# bluetooth.net
KiCad netlist of a schematic drawn in Altium Designer
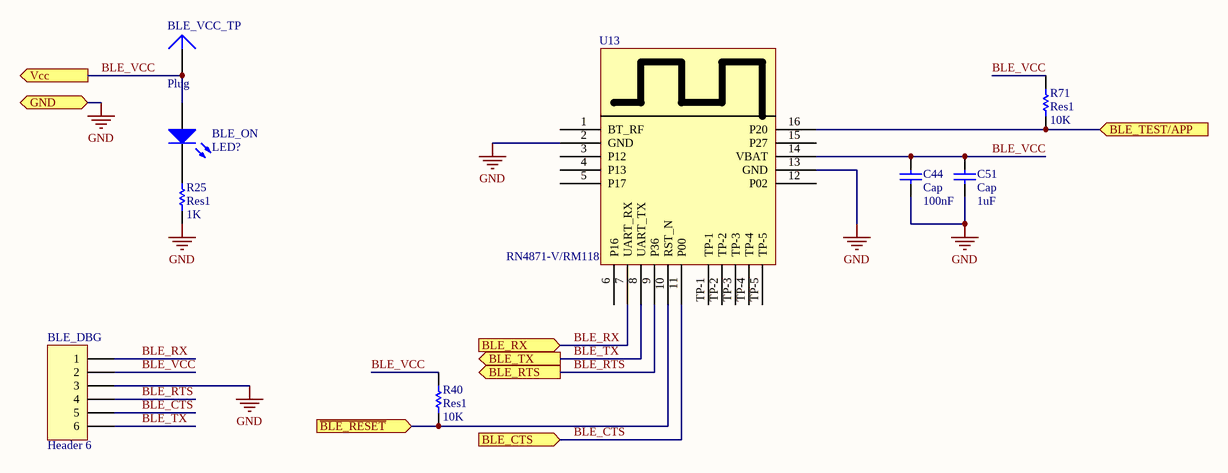
[diagram p0: bluetooth.SchDoc]

(export (version "E")
  (design (tool "Eeschema 10.0.6"))
  (components
    (comp (ref "BLE_DBG")
      (value "Header 6")
      (footprint "HDR1X6")
      (description "Header, 6-Pin")
      (fields (field (name "PUBLISHER") "Altium Limited"))
      (libsource (lib "Miscellaneous Connectors") (part "Header 6"))
    )
    (comp (ref "BLE_ON")
      (value "LED?")
      (footprint "C0603")
      (description "Typical INFRARED GaAs LED")
      (fields (field (name "PUBLISHER") "Altium Limited"))
      (libsource (lib "any") (part "LED0"))
    )
    (comp (ref "BLE_VCC_TP")
      (value "Plug")
      (footprint "PIN1")
      (fields (field (name "PUBLISHER") "Altium Limited"))
      (libsource (lib "Miscellaneous Connectors") (part "Plug"))
    )
    (comp (ref "C44")
      (value "Cap")
      (footprint "C0603")
      (description "Capacitor")
      (fields (field (name "ALTIUM_VALUE") "100nF") (field (name "PUBLISHER") "Altium Limited"))
      (libsource (lib "any") (part "Cap"))
    )
    (comp (ref "C51")
      (value "Cap")
      (footprint "C0603")
      (description "Capacitor")
      (fields (field (name "ALTIUM_VALUE") "1uF") (field (name "PUBLISHER") "Altium Limited"))
      (libsource (lib "any") (part "Cap"))
    )
    (comp (ref "R25")
      (value "Res1")
      (footprint "R0603")
      (description "Resistor")
      (fields (field (name "ALTIUM_VALUE") "1K") (field (name "PUBLISHER") "Altium Limited"))
      (libsource (lib "any") (part "Res1"))
    )
    (comp (ref "R40")
      (value "Res1")
      (footprint "R0603")
      (description "Resistor")
      (fields (field (name "ALTIUM_VALUE") "10K") (field (name "PUBLISHER") "Altium Limited"))
      (libsource (lib "Miscellaneous Devices") (part "Res1"))
    )
    (comp (ref "R71")
      (value "Res1")
      (footprint "R0603")
      (description "Resistor")
      (fields (field (name "ALTIUM_VALUE") "10K") (field (name "PUBLISHER") "Altium Limited"))
      (libsource (lib "Miscellaneous Devices") (part "Res1"))
    )
    (comp (ref "U13")
      (value "RN4871-V/RM118")
      (footprint "BM71BLES1FC2")
      (description "RN4871-V/RM118 Bluetooth 4.2 LE Mesh")
      (libsource (lib "ttn_schematic_library") (part "BM718LES1FC2"))
    )
  )
  (nets
    (net (code "1") (name "/BLE_CTS") (class "Default")
      (node (ref "BLE_DBG") (pin "5") (pinfunction "5_5") (pintype "passive"))
      (node (ref "U13") (pin "11") (pinfunction "P00_11") (pintype "passive"))
    )
    (net (code "2") (name "/BLE_RTS") (class "Default")
      (node (ref "BLE_DBG") (pin "4") (pinfunction "4_4") (pintype "passive"))
      (node (ref "U13") (pin "9") (pinfunction "P36_9") (pintype "passive"))
    )
    (net (code "3") (name "/BLE_RX") (class "Default")
      (node (ref "BLE_DBG") (pin "1") (pinfunction "1_1") (pintype "passive"))
      (node (ref "U13") (pin "7") (pinfunction "UART_RX_7") (pintype "passive"))
    )
    (net (code "4") (name "/BLE_TEST{slash}APP") (class "Default")
      (node (ref "R71") (pin "1") (pinfunction "1_1") (pintype "passive"))
      (node (ref "U13") (pin "16") (pinfunction "P20_16") (pintype "passive"))
    )
    (net (code "5") (name "/BLE_TX") (class "Default")
      (node (ref "BLE_DBG") (pin "6") (pinfunction "6_6") (pintype "passive"))
      (node (ref "U13") (pin "8") (pinfunction "UART_TX_8") (pintype "passive"))
    )
    (net (code "6") (name "/BLE_VCC") (class "Default")
      (node (ref "BLE_DBG") (pin "2") (pinfunction "2_2") (pintype "passive"))
      (node (ref "BLE_ON") (pin "1") (pinfunction "A_1") (pintype "passive"))
      (node (ref "BLE_VCC_TP") (pin "1") (pinfunction "1_1") (pintype "passive"))
      (node (ref "C44") (pin "2") (pinfunction "2_2") (pintype "passive"))
      (node (ref "C51") (pin "2") (pinfunction "2_2") (pintype "passive"))
      (node (ref "R40") (pin "2") (pinfunction "2_2") (pintype "passive"))
      (node (ref "R71") (pin "2") (pinfunction "2_2") (pintype "passive"))
      (node (ref "U13") (pin "14") (pinfunction "VBAT_14") (pintype "passive"))
    )
    (net (code "7") (name "/~{BLE_RESET}") (class "Default")
      (node (ref "R40") (pin "1") (pinfunction "1_1") (pintype "passive"))
      (node (ref "U13") (pin "10") (pinfunction "RST_N_10") (pintype "passive"))
    )
    (net (code "8") (name "GND") (class "Default")
      (node (ref "BLE_DBG") (pin "3") (pinfunction "3_3") (pintype "passive"))
      (node (ref "C44") (pin "1") (pinfunction "1_1") (pintype "passive"))
      (node (ref "C51") (pin "1") (pinfunction "1_1") (pintype "passive"))
      (node (ref "R25") (pin "1") (pinfunction "1_1") (pintype "passive"))
      (node (ref "U13") (pin "13") (pinfunction "GND_13") (pintype "passive"))
      (node (ref "U13") (pin "2") (pinfunction "GND_2") (pintype "passive"))
    )
    (net (code "9") (name "Net-(BLE_ON-K)") (class "Default")
      (node (ref "BLE_ON") (pin "2") (pinfunction "K_2") (pintype "passive"))
      (node (ref "R25") (pin "2") (pinfunction "2_2") (pintype "passive"))
    )
    (net (code "10") (name "unconnected-(U13-BT_RF-Pad1)") (class "Default")
      (node (ref "U13") (pin "1") (pinfunction "BT_RF_1") (pintype "passive"))
    )
    (net (code "11") (name "unconnected-(U13-P02-Pad12)") (class "Default")
      (node (ref "U13") (pin "12") (pinfunction "P02_12") (pintype "passive"))
    )
    (net (code "12") (name "unconnected-(U13-P12-Pad3)") (class "Default")
      (node (ref "U13") (pin "3") (pinfunction "P12_3") (pintype "passive"))
    )
    (net (code "13") (name "unconnected-(U13-P13-Pad4)") (class "Default")
      (node (ref "U13") (pin "4") (pinfunction "P13_4") (pintype "passive"))
    )
    (net (code "14") (name "unconnected-(U13-P16-Pad6)") (class "Default")
      (node (ref "U13") (pin "6") (pinfunction "P16_6") (pintype "passive"))
    )
    (net (code "15") (name "unconnected-(U13-P17-Pad5)") (class "Default")
      (node (ref "U13") (pin "5") (pinfunction "P17_5") (pintype "passive"))
    )
    (net (code "16") (name "unconnected-(U13-P27-Pad15)") (class "Default")
      (node (ref "U13") (pin "15") (pinfunction "P27_15") (pintype "passive"))
    )
    (net (code "17") (name "unconnected-(U13-PadTP-1)") (class "Default")
      (node (ref "U13") (pin "TP-1") (pinfunction "TP-1_TP-1") (pintype "passive"))
    )
    (net (code "18") (name "unconnected-(U13-PadTP-2)") (class "Default")
      (node (ref "U13") (pin "TP-2") (pinfunction "TP-2_TP-2") (pintype "passive"))
    )
    (net (code "19") (name "unconnected-(U13-PadTP-3)") (class "Default")
      (node (ref "U13") (pin "TP-3") (pinfunction "TP-3_TP-3") (pintype "passive"))
    )
    (net (code "20") (name "unconnected-(U13-PadTP-4)") (class "Default")
      (node (ref "U13") (pin "TP-4") (pinfunction "TP-4_TP-4") (pintype "passive"))
    )
    (net (code "21") (name "unconnected-(U13-PadTP-5)") (class "Default")
      (node (ref "U13") (pin "TP-5") (pinfunction "TP-5_TP-5") (pintype "passive"))
    )
  )
)
